# onStep-board-uc.net
KiCad netlist of a schematic drawn in Altium Designer
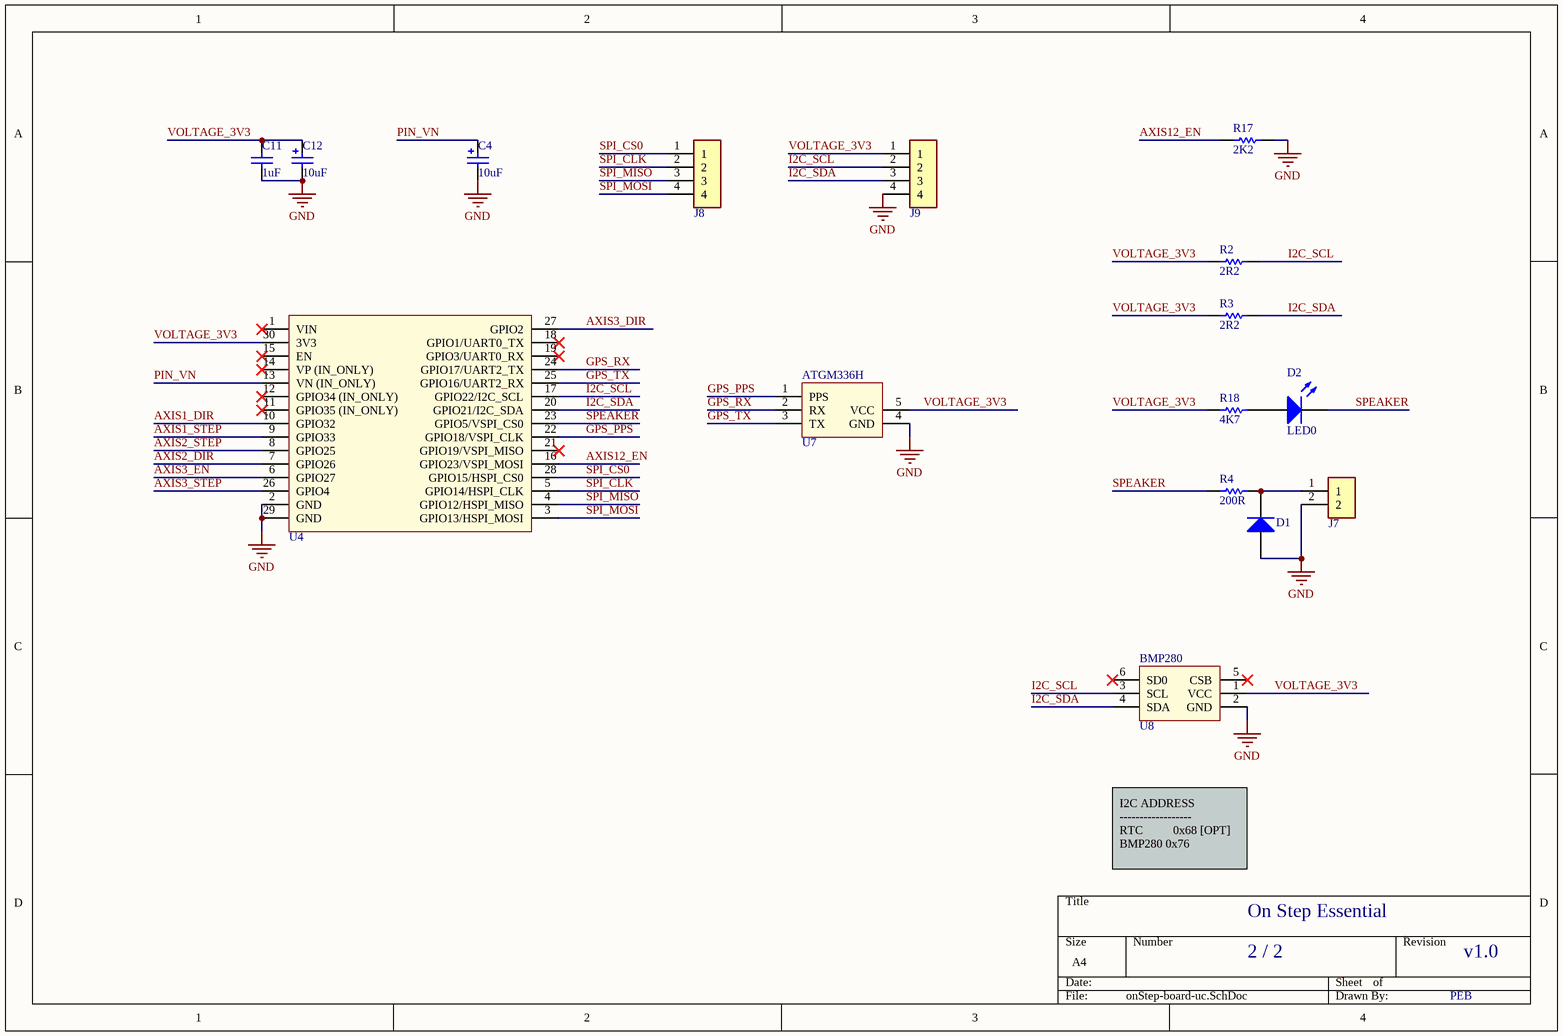
[diagram p0: onStep-board-uc.SchDoc]

(export (version "E")
  (design (tool "Eeschema 10.0.6"))
  (components
    (comp (ref "C4")
      (value "10uF")
      (footprint "WCAP-ASLL_5x5.5")
      (description "WCAP-ASLL Aluminum Electrolytic Capacitors, size Ф8x10.5mm, 25V DC, 150uF")
      (fields (field (name "PART NUMBER") "865060453006") (field (name "PUBLISHER") "Wurth Elektronik"))
      (libsource (lib "ALTIUM-WCAP-ASLL-rev17a") (part "865060453006"))
    )
    (comp (ref "C11")
      (value "1uF")
      (footprint "0805")
      (description "Capacitor")
      (fields (field (name "Comment") "Cap") (field (name "PUBLISHER") "Altium Limited"))
      (libsource (lib "Miscellaneous Devices") (part "Cap"))
    )
    (comp (ref "C12")
      (value "10uF")
      (footprint "WCAP-ASLL_5x5.5")
      (description "WCAP-ASLL Aluminum Electrolytic Capacitors, size Ф8x10.5mm, 25V DC, 150uF")
      (fields (field (name "PART NUMBER") "865060453006") (field (name "PUBLISHER") "Wurth Elektronik"))
      (libsource (lib "ALTIUM-WCAP-ASLL-rev17a") (part "865060453006"))
    )
    (comp (ref "D1")
      (value "Diode")
      (footprint "C1206")
      (description "Default Diode")
      (fields (field (name "PUBLISHER") "Altium Limited"))
      (libsource (lib "Miscellaneous Devices") (part "Diode"))
    )
    (comp (ref "D2")
      (value "LED0")
      (footprint "LED-0")
      (description "Typical INFRARED GaAs LED")
      (fields (field (name "PUBLISHER") "Altium Limited"))
      (libsource (lib "Miscellaneous Devices") (part "LED0"))
    )
    (comp (ref "J7")
      (value "SPEAKER")
      (footprint "lib_common:B2BXHALFSN")
      (description "Connector")
      (fields (field (name "MANUFACTURER_PART_NUMBER") "B2B-XH-A(LF)(SN)"))
      (libsource (lib "lib_common") (part "B2B-XH-A_LF__SN_"))
    )
    (comp (ref "J8")
      (value "SPI")
      (footprint "p4")
      (description "Connector")
      (fields (field (name "MANUFACTURER_PART_NUMBER") "B4B-XH-A(LF)(SN)"))
      (libsource (lib "lib_common") (part "B4B-XH-A_LF__SN_"))
    )
    (comp (ref "J9")
      (value "I2C")
      (footprint "p4")
      (description "Connector")
      (fields (field (name "MANUFACTURER_PART_NUMBER") "B4B-XH-A(LF)(SN)"))
      (libsource (lib "lib_common") (part "B4B-XH-A_LF__SN_"))
    )
    (comp (ref "R2")
      (value "2R2")
      (footprint "0805")
      (description "Resistor")
      (fields (field (name "Comment") "Res1") (field (name "PUBLISHER") "Altium Limited"))
      (libsource (lib "Miscellaneous Devices") (part "Res1"))
    )
    (comp (ref "R3")
      (value "2R2")
      (footprint "0805")
      (description "Resistor")
      (fields (field (name "Comment") "Res1") (field (name "PUBLISHER") "Altium Limited"))
      (libsource (lib "Miscellaneous Devices") (part "Res1"))
    )
    (comp (ref "R4")
      (value "200R")
      (footprint "0805")
      (description "Resistor")
      (fields (field (name "Comment") "Res1") (field (name "PUBLISHER") "Altium Limited"))
      (libsource (lib "Miscellaneous Devices") (part "Res1"))
    )
    (comp (ref "R17")
      (value "2K2")
      (footprint "0805")
      (description "Resistor")
      (fields (field (name "Comment") "Res1") (field (name "PUBLISHER") "Altium Limited"))
      (libsource (lib "Miscellaneous Devices") (part "Res1"))
    )
    (comp (ref "R18")
      (value "4K7")
      (footprint "0805")
      (description "Resistor")
      (fields (field (name "Comment") "Res1") (field (name "PUBLISHER") "Altium Limited"))
      (libsource (lib "Miscellaneous Devices") (part "Res1"))
    )
    (comp (ref "U4")
      (value "ESP32-WROOM-DEVKIT")
      (footprint "ESP32-WROOM-DEVKIT")
      (libsource (lib "lib_common") (part "ESP32-WROOM-DEVKIT"))
    )
    (comp (ref "U7")
      (value "ATGM336H")
      (footprint "ATGM336H")
      (libsource (lib "lib_common") (part "ATGM336H"))
    )
    (comp (ref "U8") (value "BMP280") (footprint "BMP280") (libsource (lib "lib_common") (part "BMP280")))
  )
  (nets
    (net (code "1") (name "/AXIS1_DIR") (class "Default")
      (node (ref "U4") (pin "10") (pinfunction "GPIO32_10") (pintype "passive"))
    )
    (net (code "2") (name "/AXIS1_STEP") (class "Default")
      (node (ref "U4") (pin "9") (pinfunction "GPIO33_9") (pintype "passive"))
    )
    (net (code "3") (name "/AXIS2_DIR") (class "Default")
      (node (ref "U4") (pin "7") (pinfunction "GPIO26_7") (pintype "passive"))
    )
    (net (code "4") (name "/AXIS2_STEP") (class "Default")
      (node (ref "U4") (pin "8") (pinfunction "GPIO25_8") (pintype "passive"))
    )
    (net (code "5") (name "/AXIS3_DIR") (class "Default")
      (node (ref "U4") (pin "27") (pinfunction "GPIO2_27") (pintype "passive"))
    )
    (net (code "6") (name "/AXIS3_EN") (class "Default")
      (node (ref "U4") (pin "6") (pinfunction "GPIO27_6") (pintype "passive"))
    )
    (net (code "7") (name "/AXIS3_STEP") (class "Default")
      (node (ref "U4") (pin "26") (pinfunction "GPIO4_26") (pintype "passive"))
    )
    (net (code "8") (name "/AXIS12_EN") (class "Default")
      (node (ref "R17") (pin "2") (pinfunction "2_2") (pintype "passive"))
      (node (ref "U4") (pin "16") (pinfunction "GPIO23/VSPI_MOSI_16") (pintype "passive"))
    )
    (net (code "9") (name "/GPS_PPS") (class "Default")
      (node (ref "U4") (pin "22") (pinfunction "GPIO18/VSPI_CLK_22") (pintype "passive"))
      (node (ref "U7") (pin "1") (pinfunction "PPS_1") (pintype "passive"))
    )
    (net (code "10") (name "/GPS_RX") (class "Default")
      (node (ref "U4") (pin "24") (pinfunction "GPIO17/UART2_TX_24") (pintype "passive"))
      (node (ref "U7") (pin "2") (pinfunction "RX_2") (pintype "passive"))
    )
    (net (code "11") (name "/GPS_TX") (class "Default")
      (node (ref "U4") (pin "25") (pinfunction "GPIO16/UART2_RX_25") (pintype "passive"))
      (node (ref "U7") (pin "3") (pinfunction "TX_3") (pintype "passive"))
    )
    (net (code "12") (name "/I2C_SCL") (class "Default")
      (node (ref "J9") (pin "2") (pinfunction "2_2") (pintype "passive"))
      (node (ref "R2") (pin "1") (pinfunction "1_1") (pintype "passive"))
      (node (ref "U4") (pin "17") (pinfunction "GPIO22/I2C_SCL_17") (pintype "passive"))
      (node (ref "U8") (pin "3") (pinfunction "SCL_3") (pintype "passive"))
    )
    (net (code "13") (name "/I2C_SDA") (class "Default")
      (node (ref "J9") (pin "3") (pinfunction "3_3") (pintype "passive"))
      (node (ref "R3") (pin "1") (pinfunction "1_1") (pintype "passive"))
      (node (ref "U4") (pin "20") (pinfunction "GPIO21/I2C_SDA_20") (pintype "passive"))
      (node (ref "U8") (pin "4") (pinfunction "SDA_4") (pintype "passive"))
    )
    (net (code "14") (name "/PIN_VN") (class "Default")
      (node (ref "C4") (pin "1") (pinfunction "P_1") (pintype "passive"))
      (node (ref "U4") (pin "13") (pinfunction "VN_(IN_ONLY)_13") (pintype "passive"))
    )
    (net (code "15") (name "/SPEAKER") (class "Default")
      (node (ref "D2") (pin "2") (pinfunction "K_2") (pintype "passive"))
      (node (ref "R4") (pin "2") (pinfunction "2_2") (pintype "passive"))
      (node (ref "U4") (pin "23") (pinfunction "GPIO5/VSPI_CS0_23") (pintype "passive"))
    )
    (net (code "16") (name "/SPI_CLK") (class "Default")
      (node (ref "J8") (pin "2") (pinfunction "2_2") (pintype "passive"))
      (node (ref "U4") (pin "5") (pinfunction "GPIO14/HSPI_CLK_5") (pintype "passive"))
    )
    (net (code "17") (name "/SPI_CS0") (class "Default")
      (node (ref "J8") (pin "1") (pinfunction "1_1") (pintype "passive"))
      (node (ref "U4") (pin "28") (pinfunction "GPIO15/HSPI_CS0_28") (pintype "passive"))
    )
    (net (code "18") (name "/SPI_MISO") (class "Default")
      (node (ref "J8") (pin "3") (pinfunction "3_3") (pintype "passive"))
      (node (ref "U4") (pin "4") (pinfunction "GPIO12/HSPI_MISO_4") (pintype "passive"))
    )
    (net (code "19") (name "/SPI_MOSI") (class "Default")
      (node (ref "J8") (pin "4") (pinfunction "4_4") (pintype "passive"))
      (node (ref "U4") (pin "3") (pinfunction "GPIO13/HSPI_MOSI_3") (pintype "passive"))
    )
    (net (code "20") (name "/VOLTAGE_3V3") (class "Default")
      (node (ref "C11") (pin "2") (pinfunction "2_2") (pintype "passive"))
      (node (ref "C12") (pin "1") (pinfunction "P_1") (pintype "passive"))
      (node (ref "J9") (pin "1") (pinfunction "1_1") (pintype "passive"))
      (node (ref "R18") (pin "2") (pinfunction "2_2") (pintype "passive"))
      (node (ref "R2") (pin "2") (pinfunction "2_2") (pintype "passive"))
      (node (ref "R3") (pin "2") (pinfunction "2_2") (pintype "passive"))
      (node (ref "U4") (pin "30") (pinfunction "3V3_30") (pintype "passive"))
      (node (ref "U7") (pin "5") (pinfunction "VCC_5") (pintype "passive"))
      (node (ref "U8") (pin "1") (pinfunction "VCC_1") (pintype "passive"))
    )
    (net (code "21") (name "GND") (class "Default")
      (node (ref "C11") (pin "1") (pinfunction "1_1") (pintype "passive"))
      (node (ref "C12") (pin "2") (pinfunction "N_2") (pintype "passive"))
      (node (ref "C4") (pin "2") (pinfunction "N_2") (pintype "passive"))
      (node (ref "D1") (pin "1") (pinfunction "A_1") (pintype "passive"))
      (node (ref "J7") (pin "2") (pinfunction "2_2") (pintype "passive"))
      (node (ref "J9") (pin "4") (pinfunction "4_4") (pintype "passive"))
      (node (ref "R17") (pin "1") (pinfunction "1_1") (pintype "passive"))
      (node (ref "U4") (pin "2") (pinfunction "GND_2") (pintype "passive"))
      (node (ref "U4") (pin "29") (pinfunction "GND_29") (pintype "passive"))
      (node (ref "U7") (pin "4") (pinfunction "GND_4") (pintype "passive"))
      (node (ref "U8") (pin "2") (pinfunction "GND_2") (pintype "passive"))
    )
    (net (code "22") (name "Net-(D1-K)") (class "Default")
      (node (ref "D1") (pin "2") (pinfunction "K_2") (pintype "passive"))
      (node (ref "J7") (pin "1") (pinfunction "1_1") (pintype "passive"))
      (node (ref "R4") (pin "1") (pinfunction "1_1") (pintype "passive"))
    )
    (net (code "23") (name "Net-(D2-A)") (class "Default")
      (node (ref "D2") (pin "1") (pinfunction "A_1") (pintype "passive"))
      (node (ref "R18") (pin "1") (pinfunction "1_1") (pintype "passive"))
    )
    (net (code "24") (name "unconnected-(U4-EN-Pad15)") (class "Default")
      (node (ref "U4") (pin "15") (pinfunction "EN_15") (pintype "passive+no_connect"))
    )
    (net (code "25") (name "unconnected-(U4-GPIO1{slash}UART0_TX-Pad18)") (class "Default")
      (node (ref "U4") (pin "18") (pinfunction "GPIO1/UART0_TX_18") (pintype "passive+no_connect"))
    )
    (net (code "26") (name "unconnected-(U4-GPIO3{slash}UART0_RX-Pad19)") (class "Default")
      (node (ref "U4") (pin "19") (pinfunction "GPIO3/UART0_RX_19") (pintype "passive+no_connect"))
    )
    (net (code "27") (name "unconnected-(U4-GPIO19{slash}VSPI_MISO-Pad21)") (class "Default")
      (node (ref "U4") (pin "21") (pinfunction "GPIO19/VSPI_MISO_21") (pintype "passive+no_connect"))
    )
    (net (code "28") (name "unconnected-(U4-GPIO34_(IN_ONLY)-Pad12)") (class "Default")
      (node (ref "U4") (pin "12") (pinfunction "GPIO34_(IN_ONLY)_12") (pintype "passive+no_connect"))
    )
    (net (code "29") (name "unconnected-(U4-GPIO35_(IN_ONLY)-Pad11)") (class "Default")
      (node (ref "U4") (pin "11") (pinfunction "GPIO35_(IN_ONLY)_11") (pintype "passive+no_connect"))
    )
    (net (code "30") (name "unconnected-(U4-VIN-Pad1)") (class "Default")
      (node (ref "U4") (pin "1") (pinfunction "VIN_1") (pintype "passive+no_connect"))
    )
    (net (code "31") (name "unconnected-(U4-VP_(IN_ONLY)-Pad14)") (class "Default")
      (node (ref "U4") (pin "14") (pinfunction "VP_(IN_ONLY)_14") (pintype "passive+no_connect"))
    )
    (net (code "32") (name "unconnected-(U8-CSB-Pad5)") (class "Default")
      (node (ref "U8") (pin "5") (pinfunction "CSB_5") (pintype "passive+no_connect"))
    )
    (net (code "33") (name "unconnected-(U8-SD0-Pad6)") (class "Default")
      (node (ref "U8") (pin "6") (pinfunction "SD0_6") (pintype "passive+no_connect"))
    )
  )
)
